# sensor-astable-multivibrator-v2.net
KiCad netlist of a schematic drawn in EAGLE
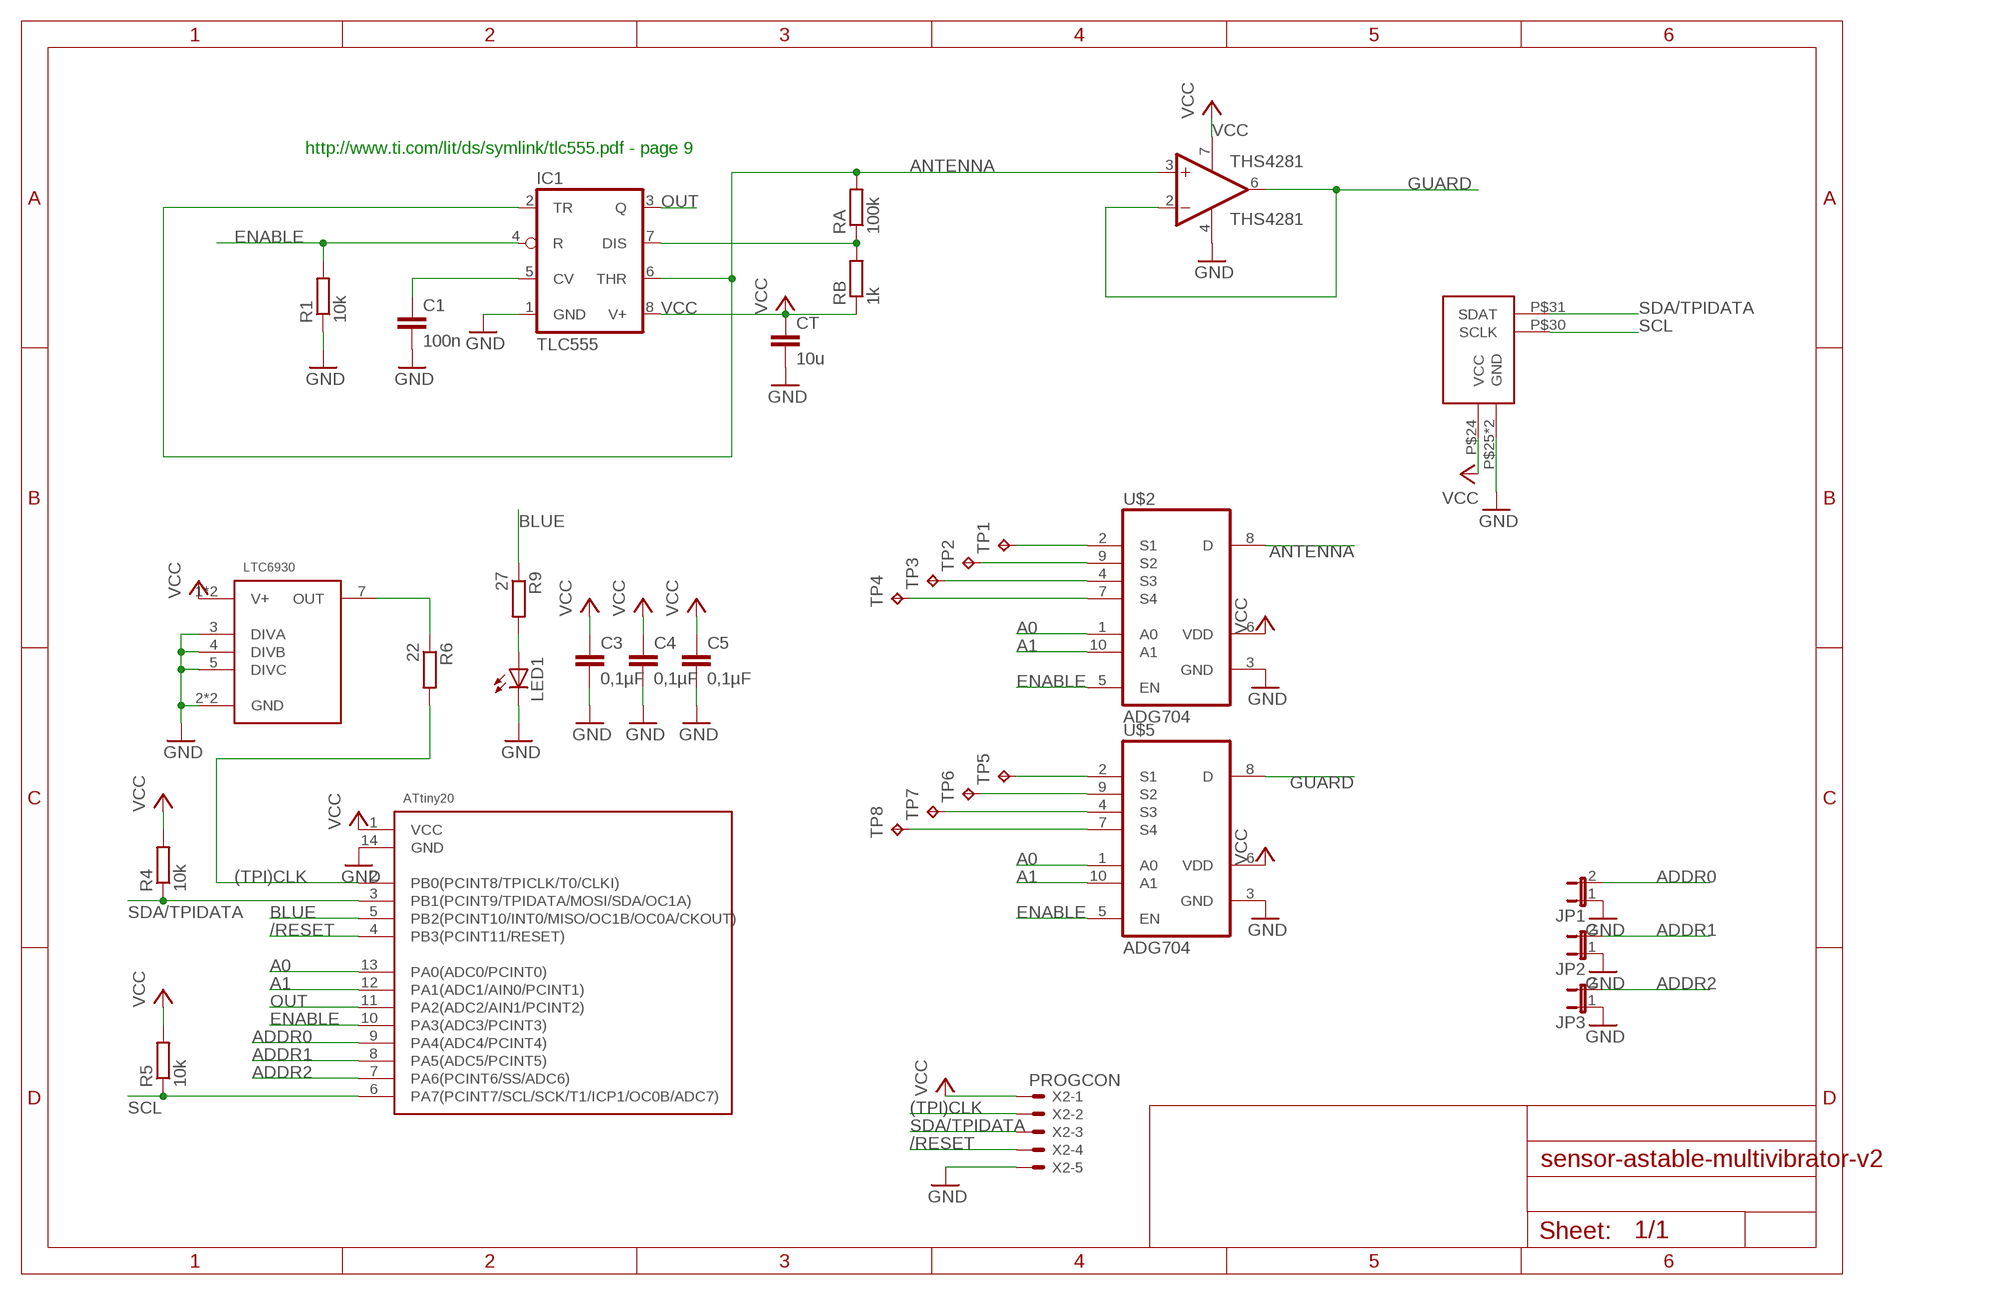
[diagram p0: schematic, sheet 1]

(export (version "E")
  (design (tool "Eeschema 10.0.6"))
  (components
    (comp (ref "C1")
      (value "100n")
      (footprint "eagle-import:C0805")
      (libsource (lib "eagle-import") (part "C-EUC0805"))
    )
    (comp (ref "C3")
      (value "0,1µF")
      (footprint "eagle-import:C0805")
      (libsource (lib "eagle-import") (part "C-EUC0805"))
    )
    (comp (ref "C4")
      (value "0,1µF")
      (footprint "eagle-import:C0805")
      (libsource (lib "eagle-import") (part "C-EUC0805"))
    )
    (comp (ref "C5")
      (value "0,1µF")
      (footprint "eagle-import:C0805")
      (libsource (lib "eagle-import") (part "C-EUC0805"))
    )
    (comp (ref "CT")
      (value "10u")
      (footprint "eagle-import:C0805")
      (libsource (lib "eagle-import") (part "C-EUC0805"))
    )
    (comp (ref "IC1")
      (value "TLC555")
      (footprint "eagle-import:SO08")
      (libsource (lib "eagle-import") (part "555DLM"))
    )
    (comp (ref "JP1")
      (value "JUMPER-2SMD-NO")
      (footprint "eagle-import:SJ_2S-NO")
      (libsource (lib "eagle-import") (part "JUMPER-2SMD-NO"))
    )
    (comp (ref "JP2")
      (value "JUMPER-2SMD-NO")
      (footprint "eagle-import:SJ_2S-NO")
      (libsource (lib "eagle-import") (part "JUMPER-2SMD-NO"))
    )
    (comp (ref "JP3")
      (value "JUMPER-2SMD-NO")
      (footprint "eagle-import:SJ_2S-NO")
      (libsource (lib "eagle-import") (part "JUMPER-2SMD-NO"))
    )
    (comp (ref "LED1")
      (value "LEDCHIPLED_0805")
      (footprint "eagle-import:CHIPLED_0805")
      (libsource (lib "eagle-import") (part "LEDCHIPLED_0805"))
    )
    (comp (ref "R1")
      (value "10k")
      (footprint "eagle-import:R0805")
      (libsource (lib "eagle-import") (part "R-EU_R0805"))
    )
    (comp (ref "R4")
      (value "10k")
      (footprint "eagle-import:R0805")
      (libsource (lib "eagle-import") (part "R-EU_R0805"))
    )
    (comp (ref "R5")
      (value "10k")
      (footprint "eagle-import:R0805")
      (libsource (lib "eagle-import") (part "R-EU_R0805"))
    )
    (comp (ref "R6")
      (value "22")
      (footprint "eagle-import:R0805")
      (libsource (lib "eagle-import") (part "R-EU_R0805"))
    )
    (comp (ref "R9")
      (value "27")
      (footprint "eagle-import:R0805")
      (libsource (lib "eagle-import") (part "R-EU_R0805"))
    )
    (comp (ref "RA")
      (value "100k")
      (footprint "eagle-import:R0805")
      (libsource (lib "eagle-import") (part "R-EU_R0805"))
    )
    (comp (ref "RB")
      (value "1k")
      (footprint "eagle-import:R0805")
      (libsource (lib "eagle-import") (part "R-EU_R0805"))
    )
    (comp (ref "THS4281")
      (value "THS4281")
      (footprint "eagle-import:SO08")
      (libsource (lib "eagle-import") (part "OPAU345"))
    )
    (comp (ref "TP1")
      (value "TPTP20SQ")
      (footprint "eagle-import:TP20SQ")
      (libsource (lib "eagle-import") (part "TPTP20SQ"))
    )
    (comp (ref "TP2")
      (value "TPTP20SQ")
      (footprint "eagle-import:TP20SQ")
      (libsource (lib "eagle-import") (part "TPTP20SQ"))
    )
    (comp (ref "TP3")
      (value "TPTP20SQ")
      (footprint "eagle-import:TP20SQ")
      (libsource (lib "eagle-import") (part "TPTP20SQ"))
    )
    (comp (ref "TP4")
      (value "TPTP20SQ")
      (footprint "eagle-import:TP20SQ")
      (libsource (lib "eagle-import") (part "TPTP20SQ"))
    )
    (comp (ref "TP5")
      (value "TPTP20SQ")
      (footprint "eagle-import:TP20SQ")
      (libsource (lib "eagle-import") (part "TPTP20SQ"))
    )
    (comp (ref "TP6")
      (value "TPTP20SQ")
      (footprint "eagle-import:TP20SQ")
      (libsource (lib "eagle-import") (part "TPTP20SQ"))
    )
    (comp (ref "TP7")
      (value "TPTP20SQ")
      (footprint "eagle-import:TP20SQ")
      (libsource (lib "eagle-import") (part "TPTP20SQ"))
    )
    (comp (ref "TP8")
      (value "TPTP20SQ")
      (footprint "eagle-import:TP20SQ")
      (libsource (lib "eagle-import") (part "TPTP20SQ"))
    )
    (comp (ref "U$1")
      (value "CAPSENSE-BREAKOUT-I2C")
      (footprint "eagle-import:JENNIC-FOOTPRINT-RB")
      (libsource (lib "eagle-import") (part "CAPSENSE-BREAKOUT-I2C"))
    )
    (comp (ref "U$2")
      (value "ADG704")
      (footprint "eagle-import:MSOP10")
      (libsource (lib "eagle-import") (part "ADG704"))
    )
    (comp (ref "U$3")
      (value "LTC6930-X.XX")
      (footprint "eagle-import:MSOP8")
      (libsource (lib "eagle-import") (part "LTC6930-X.XX"))
    )
    (comp (ref "U$4")
      (value "ATTINY20")
      (footprint "eagle-import:TSSOP14")
      (libsource (lib "eagle-import") (part "ATTINY20"))
    )
    (comp (ref "U$5")
      (value "ADG704")
      (footprint "eagle-import:MSOP10")
      (libsource (lib "eagle-import") (part "ADG704"))
    )
    (comp (ref "X2")
      (value "PROGCON")
      (footprint "eagle-import:53047-05-OCT")
      (libsource (lib "eagle-import") (part "PROGCON"))
    )
  )
  (nets
    (net (code "1") (name "/(TPI)CLK") (class "Default")
      (node (ref "R6") (pin "2") (pinfunction "2_2") (pintype "passive"))
      (node (ref "U$4") (pin "2") (pinfunction "PB0(PCINT8/TPICLK/T0/CLKI)_2") (pintype "bidirectional"))
      (node (ref "X2") (pin "2") (pinfunction "S_2") (pintype "passive"))
    )
    (net (code "2") (name "/A0") (class "Default")
      (node (ref "U$2") (pin "1") (pinfunction "A0_1") (pintype "input"))
      (node (ref "U$4") (pin "13") (pinfunction "PA0(ADC0/PCINT0)_13") (pintype "bidirectional"))
      (node (ref "U$5") (pin "1") (pinfunction "A0_1") (pintype "input"))
    )
    (net (code "3") (name "/A1") (class "Default")
      (node (ref "U$2") (pin "10") (pinfunction "A1_10") (pintype "input"))
      (node (ref "U$4") (pin "12") (pinfunction "PA1(ADC1/AIN0/PCINT1)_12") (pintype "bidirectional"))
      (node (ref "U$5") (pin "10") (pinfunction "A1_10") (pintype "input"))
    )
    (net (code "4") (name "/ADDR0") (class "Default")
      (node (ref "JP1") (pin "2") (pinfunction "2_2") (pintype "passive"))
      (node (ref "U$4") (pin "9") (pinfunction "PA4(ADC4/PCINT4)_9") (pintype "bidirectional"))
    )
    (net (code "5") (name "/ADDR1") (class "Default")
      (node (ref "JP2") (pin "2") (pinfunction "2_2") (pintype "passive"))
      (node (ref "U$4") (pin "8") (pinfunction "PA5(ADC5/PCINT5)_8") (pintype "bidirectional"))
    )
    (net (code "6") (name "/ADDR2") (class "Default")
      (node (ref "JP3") (pin "2") (pinfunction "2_2") (pintype "passive"))
      (node (ref "U$4") (pin "7") (pinfunction "PA6(PCINT6/SS/ADC6)_7") (pintype "bidirectional"))
    )
    (net (code "7") (name "/ANTENNA") (class "Default")
      (node (ref "IC1") (pin "2") (pinfunction "TR_2") (pintype "input"))
      (node (ref "IC1") (pin "6") (pinfunction "THR_6") (pintype "input"))
      (node (ref "RA") (pin "2") (pinfunction "2_2") (pintype "passive"))
      (node (ref "THS4281") (pin "3") (pinfunction "+IN_3") (pintype "input"))
      (node (ref "U$2") (pin "8") (pinfunction "D_8") (pintype "output"))
    )
    (net (code "8") (name "/BLUE") (class "Default")
      (node (ref "R9") (pin "1") (pinfunction "1_1") (pintype "passive"))
      (node (ref "U$4") (pin "5") (pinfunction "PB2(PCINT10/INT0/MISO/OC1B/OC0A/CKOUT)_5") (pintype "bidirectional"))
    )
    (net (code "9") (name "/ENABLE") (class "Default")
      (node (ref "IC1") (pin "4") (pinfunction "R_4") (pintype "input"))
      (node (ref "R1") (pin "2") (pinfunction "2_2") (pintype "passive"))
      (node (ref "U$2") (pin "5") (pinfunction "EN_5") (pintype "input"))
      (node (ref "U$4") (pin "10") (pinfunction "PA3(ADC3/PCINT3)_10") (pintype "bidirectional"))
      (node (ref "U$5") (pin "5") (pinfunction "EN_5") (pintype "input"))
    )
    (net (code "10") (name "/GUARD") (class "Default")
      (node (ref "THS4281") (pin "2") (pinfunction "-IN_2") (pintype "input"))
      (node (ref "THS4281") (pin "6") (pinfunction "OUT_6") (pintype "output"))
      (node (ref "U$5") (pin "8") (pinfunction "D_8") (pintype "output"))
    )
    (net (code "11") (name "/OUT") (class "Default")
      (node (ref "IC1") (pin "3") (pinfunction "Q_3") (pintype "output"))
      (node (ref "U$4") (pin "11") (pinfunction "PA2(ADC2/AIN1/PCINT2)_11") (pintype "bidirectional"))
    )
    (net (code "12") (name "/SCL") (class "Default")
      (node (ref "R5") (pin "1") (pinfunction "1_1") (pintype "passive"))
      (node (ref "U$1") (pin "P$30") (pinfunction "SCLK_P$30") (pintype "bidirectional"))
      (node (ref "U$4") (pin "6") (pinfunction "PA7(PCINT7/SCL/SCK/T1/ICP1/OC0B/ADC7)_6") (pintype "bidirectional"))
    )
    (net (code "13") (name "/SDA{slash}TPIDATA") (class "Default")
      (node (ref "R4") (pin "1") (pinfunction "1_1") (pintype "passive"))
      (node (ref "U$1") (pin "P$31") (pinfunction "SDAT_P$31") (pintype "bidirectional"))
      (node (ref "U$4") (pin "3") (pinfunction "PB1(PCINT9/TPIDATA/MOSI/SDA/OC1A)_3") (pintype "bidirectional"))
      (node (ref "X2") (pin "3") (pinfunction "S_3") (pintype "passive"))
    )
    (net (code "14") (name "/{slash}RESET") (class "Default")
      (node (ref "U$4") (pin "4") (pinfunction "PB3(PCINT11/RESET)_4") (pintype "bidirectional"))
      (node (ref "X2") (pin "4") (pinfunction "S_4") (pintype "passive"))
    )
    (net (code "15") (name "GND") (class "Default")
      (node (ref "C1") (pin "2") (pinfunction "2_2") (pintype "passive"))
      (node (ref "C3") (pin "2") (pinfunction "2_2") (pintype "passive"))
      (node (ref "C4") (pin "2") (pinfunction "2_2") (pintype "passive"))
      (node (ref "C5") (pin "2") (pinfunction "2_2") (pintype "passive"))
      (node (ref "CT") (pin "2") (pinfunction "2_2") (pintype "passive"))
      (node (ref "IC1") (pin "1") (pinfunction "GND_1") (pintype "power_in"))
      (node (ref "JP1") (pin "1") (pinfunction "1_1") (pintype "passive"))
      (node (ref "JP2") (pin "1") (pinfunction "1_1") (pintype "passive"))
      (node (ref "JP3") (pin "1") (pinfunction "1_1") (pintype "passive"))
      (node (ref "LED1") (pin "C") (pinfunction "C_C") (pintype "passive"))
      (node (ref "R1") (pin "1") (pinfunction "1_1") (pintype "passive"))
      (node (ref "THS4281") (pin "4") (pinfunction "V-_4") (pintype "power_in"))
      (node (ref "U$1") (pin "P$25") (pinfunction "GND_P$25") (pintype "bidirectional"))
      (node (ref "U$1") (pin "P$26") (pinfunction "GND_P$26") (pintype "bidirectional"))
      (node (ref "U$2") (pin "3") (pinfunction "GND_3") (pintype "input"))
      (node (ref "U$3") (pin "2") (pinfunction "GND_2") (pintype "bidirectional"))
      (node (ref "U$3") (pin "3") (pinfunction "DIVA_3") (pintype "bidirectional"))
      (node (ref "U$3") (pin "4") (pinfunction "DIVB_4") (pintype "bidirectional"))
      (node (ref "U$3") (pin "5") (pinfunction "DIVC_5") (pintype "bidirectional"))
      (node (ref "U$3") (pin "6") (pinfunction "GND_6") (pintype "bidirectional"))
      (node (ref "U$4") (pin "14") (pinfunction "GND_14") (pintype "bidirectional"))
      (node (ref "U$5") (pin "3") (pinfunction "GND_3") (pintype "input"))
      (node (ref "X2") (pin "5") (pinfunction "S_5") (pintype "passive"))
    )
    (net (code "16") (name "Net-(IC1-CV)") (class "Default")
      (node (ref "C1") (pin "1") (pinfunction "1_1") (pintype "passive"))
      (node (ref "IC1") (pin "5") (pinfunction "CV_5") (pintype "input"))
    )
    (net (code "17") (name "Net-(IC1-DIS)") (class "Default")
      (node (ref "IC1") (pin "7") (pinfunction "DIS_7") (pintype "input"))
      (node (ref "RA") (pin "1") (pinfunction "1_1") (pintype "passive"))
      (node (ref "RB") (pin "2") (pinfunction "2_2") (pintype "passive"))
    )
    (net (code "18") (name "Net-(LED1-PadA)") (class "Default")
      (node (ref "LED1") (pin "A") (pinfunction "A_A") (pintype "passive"))
      (node (ref "R9") (pin "2") (pinfunction "2_2") (pintype "passive"))
    )
    (net (code "19") (name "Net-(U$2-S1)") (class "Default")
      (node (ref "TP1") (pin "TP") (pinfunction "TP_TP") (pintype "input"))
      (node (ref "U$2") (pin "2") (pinfunction "S1_2") (pintype "input"))
    )
    (net (code "20") (name "Net-(U$2-S2)") (class "Default")
      (node (ref "TP2") (pin "TP") (pinfunction "TP_TP") (pintype "input"))
      (node (ref "U$2") (pin "9") (pinfunction "S2_9") (pintype "input"))
    )
    (net (code "21") (name "Net-(U$2-S3)") (class "Default")
      (node (ref "TP3") (pin "TP") (pinfunction "TP_TP") (pintype "input"))
      (node (ref "U$2") (pin "4") (pinfunction "S3_4") (pintype "input"))
    )
    (net (code "22") (name "Net-(U$2-S4)") (class "Default")
      (node (ref "TP4") (pin "TP") (pinfunction "TP_TP") (pintype "input"))
      (node (ref "U$2") (pin "7") (pinfunction "S4_7") (pintype "input"))
    )
    (net (code "23") (name "Net-(U$3-OUT)") (class "Default")
      (node (ref "R6") (pin "1") (pinfunction "1_1") (pintype "passive"))
      (node (ref "U$3") (pin "7") (pinfunction "OUT_7") (pintype "bidirectional"))
    )
    (net (code "24") (name "Net-(U$5-S1)") (class "Default")
      (node (ref "TP5") (pin "TP") (pinfunction "TP_TP") (pintype "input"))
      (node (ref "U$5") (pin "2") (pinfunction "S1_2") (pintype "input"))
    )
    (net (code "25") (name "Net-(U$5-S2)") (class "Default")
      (node (ref "TP6") (pin "TP") (pinfunction "TP_TP") (pintype "input"))
      (node (ref "U$5") (pin "9") (pinfunction "S2_9") (pintype "input"))
    )
    (net (code "26") (name "Net-(U$5-S3)") (class "Default")
      (node (ref "TP7") (pin "TP") (pinfunction "TP_TP") (pintype "input"))
      (node (ref "U$5") (pin "4") (pinfunction "S3_4") (pintype "input"))
    )
    (net (code "27") (name "Net-(U$5-S4)") (class "Default")
      (node (ref "TP8") (pin "TP") (pinfunction "TP_TP") (pintype "input"))
      (node (ref "U$5") (pin "7") (pinfunction "S4_7") (pintype "input"))
    )
    (net (code "28") (name "VCC") (class "Default")
      (node (ref "C3") (pin "1") (pinfunction "1_1") (pintype "passive"))
      (node (ref "C4") (pin "1") (pinfunction "1_1") (pintype "passive"))
      (node (ref "C5") (pin "1") (pinfunction "1_1") (pintype "passive"))
      (node (ref "CT") (pin "1") (pinfunction "1_1") (pintype "passive"))
      (node (ref "IC1") (pin "8") (pinfunction "V+_8") (pintype "power_in"))
      (node (ref "R4") (pin "2") (pinfunction "2_2") (pintype "passive"))
      (node (ref "R5") (pin "2") (pinfunction "2_2") (pintype "passive"))
      (node (ref "RB") (pin "1") (pinfunction "1_1") (pintype "passive"))
      (node (ref "THS4281") (pin "7") (pinfunction "V+_7") (pintype "power_in"))
      (node (ref "U$1") (pin "P$24") (pinfunction "VCC_P$24") (pintype "bidirectional"))
      (node (ref "U$2") (pin "6") (pinfunction "VDD_6") (pintype "input"))
      (node (ref "U$3") (pin "1") (pinfunction "V+_1") (pintype "bidirectional"))
      (node (ref "U$3") (pin "8") (pinfunction "V+_8") (pintype "bidirectional"))
      (node (ref "U$4") (pin "1") (pinfunction "VCC_1") (pintype "bidirectional"))
      (node (ref "U$5") (pin "6") (pinfunction "VDD_6") (pintype "input"))
      (node (ref "X2") (pin "1") (pinfunction "S_1") (pintype "passive"))
    )
  )
)
